# MorsePendant.net
KiCad netlist of a schematic drawn in EAGLE
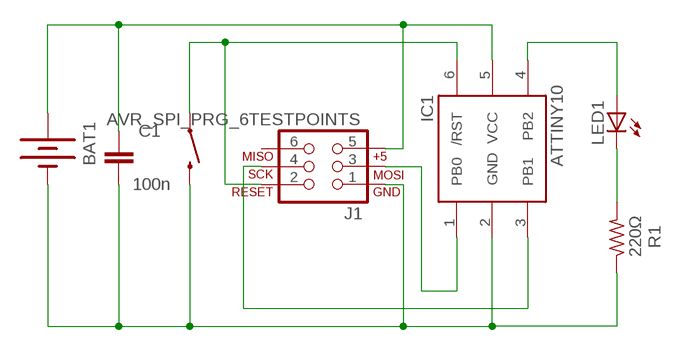
[diagram p0: schematic, sheet 1]

(export (version "E")
  (design (tool "Eeschema 10.0.6"))
  (components
    (comp (ref "BAT1")
      (value "BATTERY12MM")
      (footprint "eagle-import:BATTCON_12MM")
      (libsource (lib "eagle-import") (part "BATTERY12MM"))
    )
    (comp (ref "C1")
      (value "100n")
      (footprint "eagle-import:0603-CAP")
      (libsource (lib "eagle-import") (part "CAP0603-CAP"))
    )
    (comp (ref "IC1")
      (value "ATTINY10")
      (footprint "eagle-import:SOT23-6")
      (libsource (lib "eagle-import") (part "ATTINY10"))
    )
    (comp (ref "J1")
      (value "AVR_SPI_PRG_6TESTPOINTS")
      (footprint "eagle-import:2X3_TEST_POINTS")
      (libsource (lib "eagle-import") (part "AVR_SPI_PRG_6TESTPOINTS"))
    )
    (comp (ref "LED1")
      (value "LEDCHIPLED_0805")
      (footprint "eagle-import:CHIPLED_0805")
      (libsource (lib "eagle-import") (part "LEDCHIPLED_0805"))
    )
    (comp (ref "R1")
      (value "220Ω")
      (footprint "eagle-import:R0805")
      (libsource (lib "eagle-import") (part "R-US_R0805"))
    )
    (comp (ref "S2")
      (value "SWITCH-MOMENTARY-2SMD")
      (footprint "eagle-import:TACTILE-SWITCH-SMD")
      (libsource (lib "eagle-import") (part "SWITCH-MOMENTARY-2SMD"))
    )
  )
  (nets
    (net (code "1") (name "Net-(BAT1-+)") (class "Default")
      (node (ref "BAT1") (pin "PWR@1") (pinfunction "+_PWR@1") (pintype "power_in"))
      (node (ref "C1") (pin "1") (pinfunction "1_1") (pintype "passive"))
      (node (ref "IC1") (pin "5") (pinfunction "VCC_5") (pintype "power_in"))
      (node (ref "J1") (pin "5") (pinfunction "5_5") (pintype "passive"))
    )
    (net (code "2") (name "Net-(BAT1--)") (class "Default")
      (node (ref "BAT1") (pin "GND") (pinfunction "-_GND") (pintype "power_in"))
      (node (ref "C1") (pin "2") (pinfunction "2_2") (pintype "passive"))
      (node (ref "IC1") (pin "2") (pinfunction "GND_2") (pintype "power_in"))
      (node (ref "J1") (pin "1") (pinfunction "1_1") (pintype "passive"))
      (node (ref "R1") (pin "1") (pinfunction "1_1") (pintype "passive"))
      (node (ref "S2") (pin "3") (pinfunction "2_3") (pintype "passive"))
    )
    (net (code "3") (name "Net-(IC1-PB0)") (class "Default")
      (node (ref "IC1") (pin "1") (pinfunction "PB0_1") (pintype "bidirectional"))
      (node (ref "J1") (pin "3") (pinfunction "3_3") (pintype "passive"))
    )
    (net (code "4") (name "Net-(IC1-PB1)") (class "Default")
      (node (ref "IC1") (pin "3") (pinfunction "PB1_3") (pintype "bidirectional"))
      (node (ref "J1") (pin "4") (pinfunction "4_4") (pintype "passive"))
    )
    (net (code "5") (name "Net-(IC1-PB2)") (class "Default")
      (node (ref "IC1") (pin "4") (pinfunction "PB2_4") (pintype "bidirectional"))
      (node (ref "LED1") (pin "A") (pinfunction "A_A") (pintype "passive"))
    )
    (net (code "6") (name "Net-(IC1-{slash}RST)") (class "Default")
      (node (ref "IC1") (pin "6") (pinfunction "/RST_6") (pintype "bidirectional"))
      (node (ref "J1") (pin "2") (pinfunction "2_2") (pintype "passive"))
      (node (ref "S2") (pin "1") (pinfunction "1_1") (pintype "passive"))
    )
    (net (code "7") (name "Net-(LED1-PadC)") (class "Default")
      (node (ref "LED1") (pin "C") (pinfunction "C_C") (pintype "passive"))
      (node (ref "R1") (pin "2") (pinfunction "2_2") (pintype "passive"))
    )
    (net (code "8") (name "unconnected-(J1-Pad6)") (class "Default")
      (node (ref "J1") (pin "6") (pinfunction "6_6") (pintype "passive"))
    )
  )
)
